# Sensors.net
KiCad netlist of a schematic drawn in Altium Designer
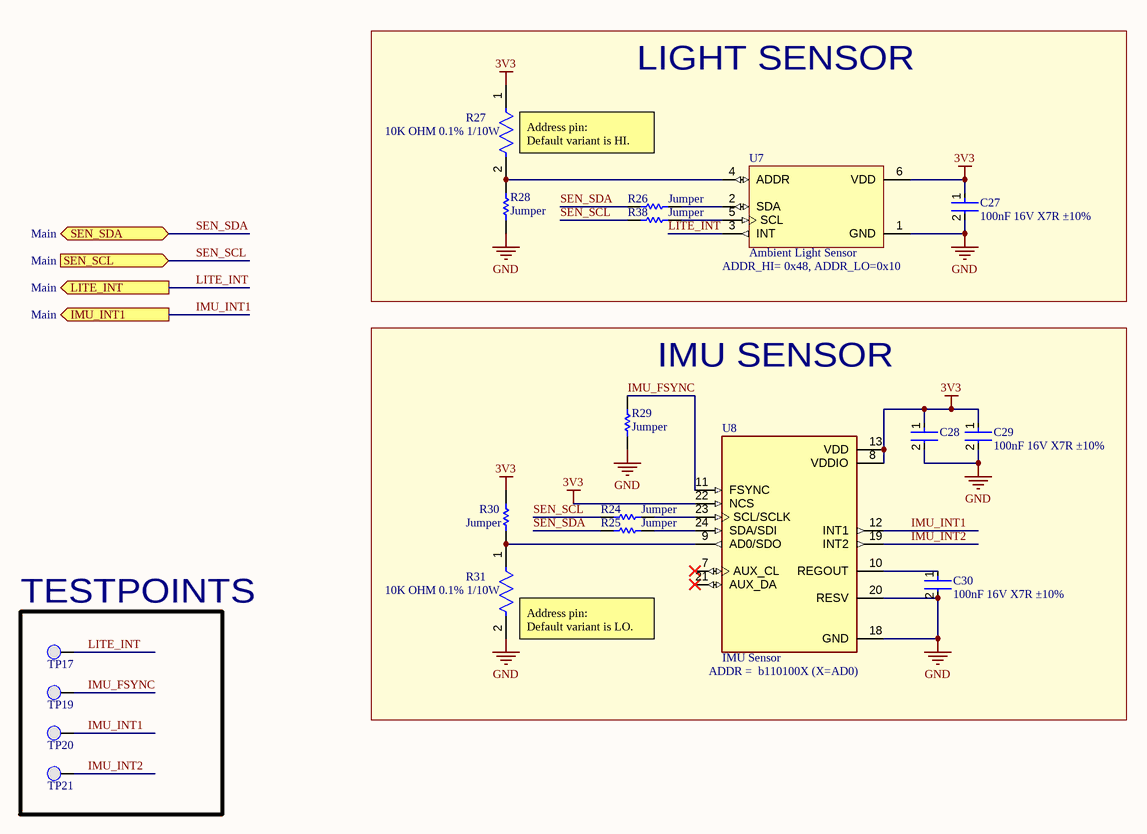
[diagram p0: Sensors.SchDoc]

(export (version "E")
  (design (tool "Eeschema 10.0.6"))
  (components
    (comp (ref "C27")
      (value "100nF 16V X7R ±10%")
      (footprint "FP-CL10-IPC_A")
      (description "Cap Ceramic 100nF 16V X7R ±10% Pad SMD 0603 +125°C T/R CL10B104KO8NNNL")
      (fields (field (name "VOLTAGE") "16V") (field (name "TOLERANCE") "10%"))
      (libsource (lib "Altium Content Vault") (part "b4654b650e69147ec39a6b967a45e02"))
    )
    (comp (ref "C28")
      (value "100nF 16V X7R ±10%")
      (footprint "FP-CL10-IPC_A")
      (description "Cap Ceramic 100nF 16V X7R ±10% Pad SMD 0603 +125°C T/R CL10B104KO8NNNL")
      (fields (field (name "VOLTAGE") "16V") (field (name "TOLERANCE") "10%"))
      (libsource (lib "Altium Content Vault") (part "b4654b650e69147ec39a6b967a45e02"))
    )
    (comp (ref "C29")
      (value "100nF 16V X7R ±10%")
      (footprint "FP-CL10-IPC_A")
      (description "Cap Ceramic 100nF 16V X7R ±10% Pad SMD 0603 +125°C T/R CL10B104KO8NNNL")
      (fields (field (name "VOLTAGE") "16V") (field (name "TOLERANCE") "10%"))
      (libsource (lib "Altium Content Vault") (part "b4654b650e69147ec39a6b967a45e02"))
    )
    (comp (ref "C30")
      (value "100nF 16V X7R ±10%")
      (footprint "FP-CL10-IPC_A")
      (description "Cap Ceramic 100nF 16V X7R ±10% Pad SMD 0603 +125°C T/R CL10B104KO8NNNL")
      (fields (field (name "VOLTAGE") "16V") (field (name "TOLERANCE") "10%"))
      (libsource (lib "Altium Content Vault") (part "b4654b650e69147ec39a6b967a45e02"))
    )
    (comp (ref "R24")
      (value "Jumper")
      (footprint "RESC0603(1608)_N")
      (description "Jumper 0603 (1608 Metric)")
      (fields (field (name "POWER") "None"))
      (libsource (lib "Altium Content Vault") (part "RES"))
    )
    (comp (ref "R25")
      (value "Jumper")
      (footprint "RESC0603(1608)_N")
      (description "Jumper 0603 (1608 Metric)")
      (fields (field (name "POWER") "None"))
      (libsource (lib "Altium Content Vault") (part "RES"))
    )
    (comp (ref "R26")
      (value "Jumper")
      (footprint "RESC0603(1608)_N")
      (description "Jumper 0603 (1608 Metric)")
      (fields (field (name "POWER") "None"))
      (libsource (lib "Altium Content Vault") (part "RES"))
    )
    (comp (ref "R27")
      (value "10K OHM 0.1% 1/10W")
      (footprint "FP-RT0603-MFG")
      (description "RES SMD 10K OHM 0.1% 1/10W 0603 RT0603BRB0710KL")
      (fields
        (field (name "MANUFACTURER") "Yageo")
        (field (name "MANUFACTURER PART NUMBER") "RT0603BRB0710KL")
      )
      (libsource (lib "Altium Content Vault") (part "1029c3af85768c4190bb7ad29bc67b5"))
    )
    (comp (ref "R28")
      (value "Jumper")
      (footprint "RESC0603(1608)_N")
      (description "Jumper 0603 (1608 Metric)")
      (fields (field (name "POWER") "None"))
      (libsource (lib "Altium Content Vault") (part "RES"))
    )
    (comp (ref "R29")
      (value "Jumper")
      (footprint "RESC0603(1608)_N")
      (description "Jumper 0603 (1608 Metric)")
      (fields (field (name "POWER") "None"))
      (libsource (lib "Altium Content Vault") (part "RES"))
    )
    (comp (ref "R30")
      (value "Jumper")
      (footprint "RESC0603(1608)_N")
      (description "Jumper 0603 (1608 Metric)")
      (fields (field (name "POWER") "None"))
      (libsource (lib "Altium Content Vault") (part "RES"))
    )
    (comp (ref "R31")
      (value "10K OHM 0.1% 1/10W")
      (footprint "FP-RT0603-MFG")
      (description "RES SMD 10K OHM 0.1% 1/10W 0603 RT0603BRB0710KL")
      (fields
        (field (name "MANUFACTURER") "Yageo")
        (field (name "MANUFACTURER PART NUMBER") "RT0603BRB0710KL")
      )
      (libsource (lib "Altium Content Vault") (part "1029c3af85768c4190bb7ad29bc67b5"))
    )
    (comp (ref "R38")
      (value "Jumper")
      (footprint "RESC0603(1608)_N")
      (description "Jumper 0603 (1608 Metric)")
      (fields (field (name "POWER") "None"))
      (libsource (lib "Altium Content Vault") (part "RES"))
    )
    (comp (ref "TP17")
      (value "0.1\" Pad")
      (footprint "PCBComponent")
      (libsource (lib "Components - 12.02.20 - 18.05") (part "0.1{dblquote} Pad-A.4"))
    )
    (comp (ref "TP19")
      (value "0.1\" Pad")
      (footprint "PCBComponent")
      (libsource (lib "Components - 12.02.20 - 18.05") (part "0.1{dblquote} Pad-A.4"))
    )
    (comp (ref "TP20")
      (value "0.1\" Pad")
      (footprint "PCBComponent")
      (libsource (lib "Components - 12.02.20 - 18.05") (part "0.1{dblquote} Pad-A.4"))
    )
    (comp (ref "TP21")
      (value "0.1\" Pad")
      (footprint "PCBComponent")
      (libsource (lib "Components - 12.02.20 - 18.05") (part "0.1{dblquote} Pad-A.4"))
    )
    (comp (ref "U7")
      (value "Ambient Light Sensor")
      (footprint "ProtoWatch_PcbLib:VISHAY_VEML6030_2X2X0.87")
      (description "Optical Sensor Ambient 550nm IÂ²C 6-SMD, No Lead")
      (fields (field (name "MF") "Vishay") (field (name "MP") "VEML6030"))
      (libsource (lib "ProtoWatch_SchLib") (part "VEML6030"))
    )
    (comp (ref "U8")
      (value "IMU Sensor")
      (footprint "ProtoWatch_PcbLib:ICM-20649")
      (description "Accelerometer, Gyroscope, Temperature, 6 Axis Sensor IÂ²C, SPI Output")
      (fields (field (name "MF") "TDK InvenSense") (field (name "MP") "ICM-20649"))
      (libsource (lib "ProtoWatch_SchLib") (part "ICM-20649"))
    )
  )
  (nets
    (net (code "1") (name "/IMU_FSYNC") (class "Default")
      (node (ref "R29") (pin "2") (pinfunction "2_2") (pintype "passive"))
      (node (ref "TP19") (pin "1") (pinfunction "PAD_1") (pintype "passive"))
      (node (ref "U8") (pin "11") (pinfunction "FSYNC_11") (pintype "input"))
    )
    (net (code "2") (name "/IMU_INT1") (class "Default")
      (node (ref "TP20") (pin "1") (pinfunction "PAD_1") (pintype "passive"))
      (node (ref "U8") (pin "12") (pinfunction "INT1_12") (pintype "output"))
    )
    (net (code "3") (name "/IMU_INT2") (class "Default")
      (node (ref "TP21") (pin "1") (pinfunction "PAD_1") (pintype "passive"))
      (node (ref "U8") (pin "19") (pinfunction "INT2_19") (pintype "output"))
    )
    (net (code "4") (name "/LITE_INT") (class "Default")
      (node (ref "TP17") (pin "1") (pinfunction "PAD_1") (pintype "passive"))
      (node (ref "U7") (pin "3") (pinfunction "INT_3") (pintype "output"))
    )
    (net (code "5") (name "/SEN_SCL") (class "Default")
      (node (ref "R24") (pin "2") (pinfunction "2_2") (pintype "passive"))
      (node (ref "R38") (pin "2") (pinfunction "2_2") (pintype "passive"))
    )
    (net (code "6") (name "/SEN_SDA") (class "Default")
      (node (ref "R25") (pin "2") (pinfunction "2_2") (pintype "passive"))
      (node (ref "R26") (pin "2") (pinfunction "2_2") (pintype "passive"))
    )
    (net (code "7") (name "3V3") (class "Default")
      (node (ref "C27") (pin "1") (pinfunction "1_1") (pintype "passive"))
      (node (ref "C28") (pin "1") (pinfunction "1_1") (pintype "passive"))
      (node (ref "C29") (pin "1") (pinfunction "1_1") (pintype "passive"))
      (node (ref "R27") (pin "1") (pinfunction "1_1") (pintype "passive"))
      (node (ref "R30") (pin "2") (pinfunction "2_2") (pintype "passive"))
      (node (ref "U7") (pin "6") (pinfunction "VDD_6") (pintype "power_in"))
      (node (ref "U8") (pin "13") (pinfunction "VDD_13") (pintype "power_in"))
      (node (ref "U8") (pin "22") (pinfunction "NCS_22") (pintype "input"))
      (node (ref "U8") (pin "8") (pinfunction "VDDIO_8") (pintype "power_in"))
    )
    (net (code "8") (name "GND") (class "Default")
      (node (ref "C27") (pin "2") (pinfunction "2_2") (pintype "passive"))
      (node (ref "C28") (pin "2") (pinfunction "2_2") (pintype "passive"))
      (node (ref "C29") (pin "2") (pinfunction "2_2") (pintype "passive"))
      (node (ref "C30") (pin "2") (pinfunction "2_2") (pintype "passive"))
      (node (ref "R28") (pin "1") (pinfunction "1_1") (pintype "passive"))
      (node (ref "R29") (pin "1") (pinfunction "1_1") (pintype "passive"))
      (node (ref "R31") (pin "2") (pinfunction "2_2") (pintype "passive"))
      (node (ref "U7") (pin "1") (pinfunction "GND_1") (pintype "power_in"))
      (node (ref "U8") (pin "18") (pinfunction "GND_18") (pintype "power_in"))
      (node (ref "U8") (pin "20") (pinfunction "RESV_20") (pintype "passive"))
    )
    (net (code "9") (name "Net-(U7-ADDR)") (class "Default")
      (node (ref "R27") (pin "2") (pinfunction "2_2") (pintype "passive"))
      (node (ref "R28") (pin "2") (pinfunction "2_2") (pintype "passive"))
      (node (ref "U7") (pin "4") (pinfunction "ADDR_4") (pintype "bidirectional"))
    )
    (net (code "10") (name "Net-(U7-SCL)") (class "Default")
      (node (ref "R38") (pin "1") (pinfunction "1_1") (pintype "passive"))
      (node (ref "U7") (pin "5") (pinfunction "SCL_5") (pintype "input"))
    )
    (net (code "11") (name "Net-(U7-SDA)") (class "Default")
      (node (ref "R26") (pin "1") (pinfunction "1_1") (pintype "passive"))
      (node (ref "U7") (pin "2") (pinfunction "SDA_2") (pintype "bidirectional"))
    )
    (net (code "12") (name "Net-(U8-AD0{slash}SDO)") (class "Default")
      (node (ref "R30") (pin "1") (pinfunction "1_1") (pintype "passive"))
      (node (ref "R31") (pin "1") (pinfunction "1_1") (pintype "passive"))
      (node (ref "U8") (pin "9") (pinfunction "AD0/SDO_9") (pintype "output"))
    )
    (net (code "13") (name "Net-(U8-REGOUT)") (class "Default")
      (node (ref "C30") (pin "1") (pinfunction "1_1") (pintype "passive"))
      (node (ref "U8") (pin "10") (pinfunction "REGOUT_10") (pintype "passive"))
    )
    (net (code "14") (name "Net-(U8-SCL{slash}SCLK)") (class "Default")
      (node (ref "R24") (pin "1") (pinfunction "1_1") (pintype "passive"))
      (node (ref "U8") (pin "23") (pinfunction "SCL/SCLK_23") (pintype "input"))
    )
    (net (code "15") (name "Net-(U8-SDA{slash}SDI)") (class "Default")
      (node (ref "R25") (pin "1") (pinfunction "1_1") (pintype "passive"))
      (node (ref "U8") (pin "24") (pinfunction "SDA/SDI_24") (pintype "input"))
    )
    (net (code "16") (name "unconnected-(U8-AUX_CL-Pad7)") (class "Default")
      (node (ref "U8") (pin "7") (pinfunction "AUX_CL_7") (pintype "bidirectional+no_connect"))
    )
    (net (code "17") (name "unconnected-(U8-AUX_DA-Pad21)") (class "Default")
      (node (ref "U8") (pin "21") (pinfunction "AUX_DA_21") (pintype "bidirectional+no_connect"))
    )
  )
)
